# PCB_project.net
KiCad netlist of a schematic drawn in EAGLE
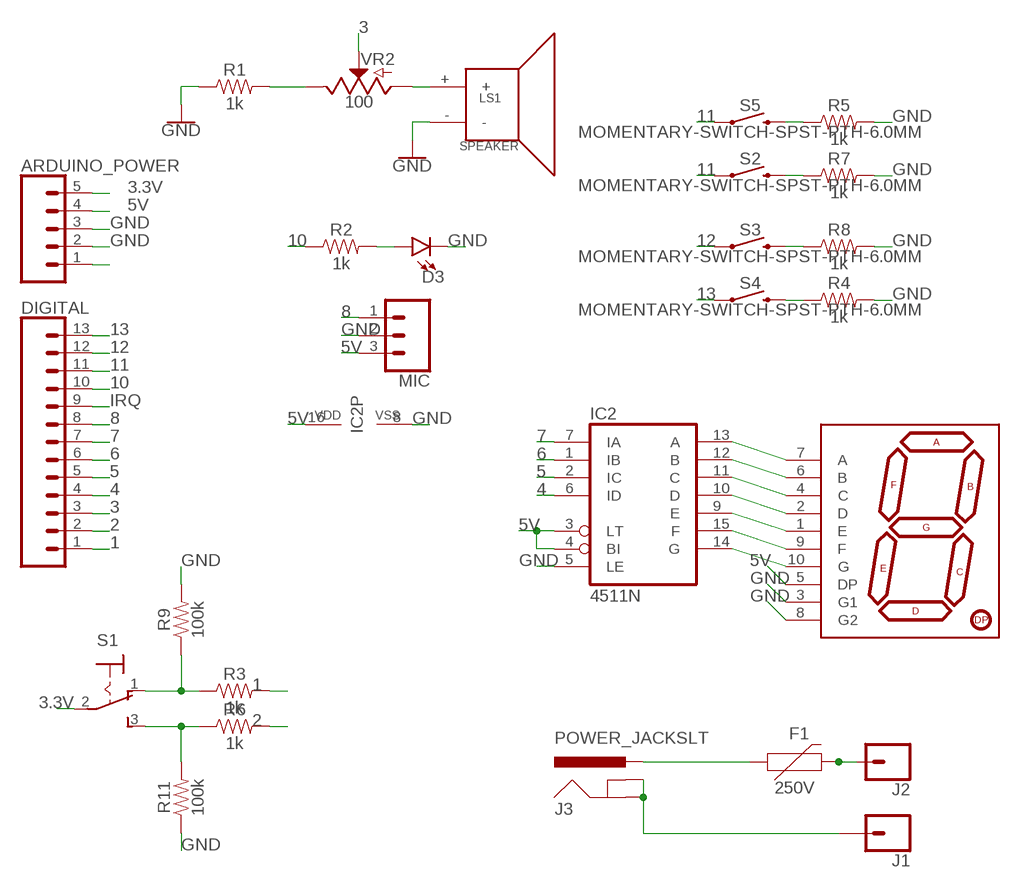
[diagram p0: schematic, sheet 1]

(export (version "E")
  (design (tool "Eeschema 10.0.6"))
  (components
    (comp (ref "ARDUINO_POWER")
      (value "CONN_05")
      (footprint "eagle-import:1X05")
      (libsource (lib "eagle-import") (part "CONN_05"))
    )
    (comp (ref "D3")
      (value "LED-3MM-NO_SILK")
      (footprint "eagle-import:LED_3MM-NS")
      (libsource (lib "eagle-import") (part "LED-3MM-NO_SILK"))
    )
    (comp (ref "DIGITAL")
      (value "CONN_13")
      (footprint "eagle-import:1X13")
      (libsource (lib "eagle-import") (part "CONN_13"))
    )
    (comp (ref "F1")
      (value "250V")
      (footprint "eagle-import:1206")
      (libsource (lib "eagle-import") (part "PPTC_HALF-AMP"))
    )
    (comp (ref "IC2")
      (value "4511N")
      (footprint "eagle-import:DIL16")
      (libsource (lib "eagle-import") (part "4511N"))
    )
    (comp (ref "J1")
      (value "CONN_01")
      (footprint "eagle-import:1X01")
      (libsource (lib "eagle-import") (part "CONN_01"))
    )
    (comp (ref "J2")
      (value "CONN_01")
      (footprint "eagle-import:1X01")
      (libsource (lib "eagle-import") (part "CONN_01"))
    )
    (comp (ref "J3")
      (value "POWER_JACKSLT")
      (footprint "eagle-import:POWER_JACK_SLOT")
      (libsource (lib "eagle-import") (part "POWER_JACKSLT"))
    )
    (comp (ref "LS1")
      (value "SPEAKER")
      (footprint "eagle-import:PCB_MOUNT_SPEAKER")
      (libsource (lib "eagle-import") (part "SPEAKER"))
    )
    (comp (ref "MIC")
      (value "CONN_03")
      (footprint "eagle-import:1X03")
      (libsource (lib "eagle-import") (part "CONN_03"))
    )
    (comp (ref "R1")
      (value "1k")
      (footprint "eagle-import:AXIAL-0.3")
      (libsource (lib "eagle-import") (part "1KOHM-HORIZ-1/4W-1%"))
    )
    (comp (ref "R2")
      (value "1k")
      (footprint "eagle-import:AXIAL-0.3")
      (libsource (lib "eagle-import") (part "1KOHM-HORIZ-1/4W-1%"))
    )
    (comp (ref "R3")
      (value "1k")
      (footprint "eagle-import:AXIAL-0.3")
      (libsource (lib "eagle-import") (part "1KOHM-HORIZ-1/4W-1%"))
    )
    (comp (ref "R4")
      (value "1k")
      (footprint "eagle-import:AXIAL-0.3")
      (libsource (lib "eagle-import") (part "1KOHM-HORIZ-1/4W-1%"))
    )
    (comp (ref "R5")
      (value "1k")
      (footprint "eagle-import:AXIAL-0.3")
      (libsource (lib "eagle-import") (part "1KOHM-HORIZ-1/4W-1%"))
    )
    (comp (ref "R6")
      (value "1k")
      (footprint "eagle-import:AXIAL-0.3")
      (libsource (lib "eagle-import") (part "1KOHM-HORIZ-1/4W-1%"))
    )
    (comp (ref "R7")
      (value "1k")
      (footprint "eagle-import:AXIAL-0.3")
      (libsource (lib "eagle-import") (part "1KOHM-HORIZ-1/4W-1%"))
    )
    (comp (ref "R8")
      (value "1k")
      (footprint "eagle-import:AXIAL-0.3")
      (libsource (lib "eagle-import") (part "1KOHM-HORIZ-1/4W-1%"))
    )
    (comp (ref "R9")
      (value "100k")
      (footprint "eagle-import:AXIAL-0.3")
      (libsource (lib "eagle-import") (part "100KOHM-HORIZ-1/4W-1%"))
    )
    (comp (ref "R11")
      (value "100k")
      (footprint "eagle-import:AXIAL-0.3")
      (libsource (lib "eagle-import") (part "100KOHM-HORIZ-1/4W-1%"))
    )
    (comp (ref "S1")
      (value "320-916")
      (footprint "eagle-import:320-916")
      (libsource (lib "eagle-import") (part "320-916"))
    )
    (comp (ref "S2")
      (value "MOMENTARY-SWITCH-SPST-PTH-6.0MM")
      (footprint "eagle-import:TACTILE_SWITCH_PTH_6.0MM")
      (libsource (lib "eagle-import") (part "MOMENTARY-SWITCH-SPST-PTH-6.0MM"))
    )
    (comp (ref "S3")
      (value "MOMENTARY-SWITCH-SPST-PTH-6.0MM")
      (footprint "eagle-import:TACTILE_SWITCH_PTH_6.0MM")
      (libsource (lib "eagle-import") (part "MOMENTARY-SWITCH-SPST-PTH-6.0MM"))
    )
    (comp (ref "S4")
      (value "MOMENTARY-SWITCH-SPST-PTH-6.0MM")
      (footprint "eagle-import:TACTILE_SWITCH_PTH_6.0MM")
      (libsource (lib "eagle-import") (part "MOMENTARY-SWITCH-SPST-PTH-6.0MM"))
    )
    (comp (ref "S5")
      (value "MOMENTARY-SWITCH-SPST-PTH-6.0MM")
      (footprint "eagle-import:TACTILE_SWITCH_PTH_6.0MM")
      (libsource (lib "eagle-import") (part "MOMENTARY-SWITCH-SPST-PTH-6.0MM"))
    )
    (comp (ref "U$1")
      (value "YSD-160AB3C-8")
      (footprint "eagle-import:7-SEGMENT-1_PTH")
      (libsource (lib "eagle-import") (part "7-SEGMENT-1DIGIT-1INCH-BLUE"))
    )
    (comp (ref "VR2")
      (value "100")
      (footprint "eagle-import:POT-PTH-ALPS")
      (libsource (lib "eagle-import") (part "POTENTIOMETER-PTH-9MM-1/20W-20%"))
    )
  )
  (nets
    (net (code "1") (name "/1") (class "Default")
      (node (ref "DIGITAL") (pin "1") (pinfunction "1_1") (pintype "passive"))
      (node (ref "R3") (pin "P$2") (pinfunction "2_P$2") (pintype "passive"))
    )
    (net (code "2") (name "/2") (class "Default")
      (node (ref "DIGITAL") (pin "2") (pinfunction "2_2") (pintype "passive"))
      (node (ref "R6") (pin "P$2") (pinfunction "2_P$2") (pintype "passive"))
    )
    (net (code "3") (name "/3") (class "Default")
      (node (ref "DIGITAL") (pin "3") (pinfunction "3_3") (pintype "passive"))
      (node (ref "VR2") (pin "P$2") (pinfunction "S_P$2") (pintype "passive"))
    )
    (net (code "4") (name "/3.3V") (class "Default")
      (node (ref "ARDUINO_POWER") (pin "5") (pinfunction "5_5") (pintype "passive"))
      (node (ref "S1") (pin "2") (pinfunction "P_2") (pintype "passive"))
    )
    (net (code "5") (name "/4") (class "Default")
      (node (ref "DIGITAL") (pin "4") (pinfunction "4_4") (pintype "passive"))
      (node (ref "IC2") (pin "6") (pinfunction "ID_6") (pintype "input"))
    )
    (net (code "6") (name "/5") (class "Default")
      (node (ref "DIGITAL") (pin "5") (pinfunction "5_5") (pintype "passive"))
      (node (ref "IC2") (pin "2") (pinfunction "IC_2") (pintype "input"))
    )
    (net (code "7") (name "/5V") (class "Default")
      (node (ref "ARDUINO_POWER") (pin "4") (pinfunction "4_4") (pintype "passive"))
      (node (ref "IC2") (pin "16") (pinfunction "VDD_16") (pintype "power_in"))
      (node (ref "IC2") (pin "3") (pinfunction "LT_3") (pintype "input"))
      (node (ref "IC2") (pin "4") (pinfunction "BI_4") (pintype "input"))
      (node (ref "MIC") (pin "3") (pinfunction "3_3") (pintype "passive"))
      (node (ref "U$1") (pin "5") (pinfunction "DP_5") (pintype "bidirectional"))
    )
    (net (code "8") (name "/6") (class "Default")
      (node (ref "DIGITAL") (pin "6") (pinfunction "6_6") (pintype "passive"))
      (node (ref "IC2") (pin "1") (pinfunction "IB_1") (pintype "input"))
    )
    (net (code "9") (name "/7") (class "Default")
      (node (ref "DIGITAL") (pin "7") (pinfunction "7_7") (pintype "passive"))
      (node (ref "IC2") (pin "7") (pinfunction "IA_7") (pintype "input"))
    )
    (net (code "10") (name "/8") (class "Default")
      (node (ref "DIGITAL") (pin "8") (pinfunction "8_8") (pintype "passive"))
      (node (ref "MIC") (pin "1") (pinfunction "1_1") (pintype "passive"))
    )
    (net (code "11") (name "/10") (class "Default")
      (node (ref "DIGITAL") (pin "10") (pinfunction "10_10") (pintype "passive"))
      (node (ref "R2") (pin "P$1") (pinfunction "1_P$1") (pintype "passive"))
    )
    (net (code "12") (name "/11") (class "Default")
      (node (ref "DIGITAL") (pin "11") (pinfunction "11_11") (pintype "passive"))
      (node (ref "S2") (pin "1") (pinfunction "1_1") (pintype "passive"))
      (node (ref "S5") (pin "1") (pinfunction "1_1") (pintype "passive"))
    )
    (net (code "13") (name "/12") (class "Default")
      (node (ref "DIGITAL") (pin "12") (pinfunction "12_12") (pintype "passive"))
      (node (ref "S3") (pin "1") (pinfunction "1_1") (pintype "passive"))
    )
    (net (code "14") (name "/13") (class "Default")
      (node (ref "DIGITAL") (pin "13") (pinfunction "13_13") (pintype "passive"))
      (node (ref "S4") (pin "1") (pinfunction "1_1") (pintype "passive"))
    )
    (net (code "15") (name "/IRQ") (class "Default")
      (node (ref "DIGITAL") (pin "9") (pinfunction "9_9") (pintype "passive"))
    )
    (net (code "16") (name "GND") (class "Default")
      (node (ref "ARDUINO_POWER") (pin "2") (pinfunction "2_2") (pintype "passive"))
      (node (ref "ARDUINO_POWER") (pin "3") (pinfunction "3_3") (pintype "passive"))
      (node (ref "D3") (pin "K") (pinfunction "C_K") (pintype "passive"))
      (node (ref "IC2") (pin "5") (pinfunction "LE_5") (pintype "input"))
      (node (ref "IC2") (pin "8") (pinfunction "VSS_8") (pintype "power_in"))
      (node (ref "LS1") (pin "-") (pinfunction "-_-") (pintype "bidirectional"))
      (node (ref "MIC") (pin "2") (pinfunction "2_2") (pintype "passive"))
      (node (ref "R1") (pin "P$1") (pinfunction "1_P$1") (pintype "passive"))
      (node (ref "R11") (pin "P$1") (pinfunction "1_P$1") (pintype "passive"))
      (node (ref "R4") (pin "P$2") (pinfunction "2_P$2") (pintype "passive"))
      (node (ref "R5") (pin "P$2") (pinfunction "2_P$2") (pintype "passive"))
      (node (ref "R7") (pin "P$2") (pinfunction "2_P$2") (pintype "passive"))
      (node (ref "R8") (pin "P$2") (pinfunction "2_P$2") (pintype "passive"))
      (node (ref "R9") (pin "P$2") (pinfunction "2_P$2") (pintype "passive"))
      (node (ref "U$1") (pin "3") (pinfunction "G1_3") (pintype "bidirectional"))
      (node (ref "U$1") (pin "8") (pinfunction "G2_8") (pintype "bidirectional"))
    )
    (net (code "17") (name "Net-(F1-Pad1)") (class "Default")
      (node (ref "F1") (pin "1") (pinfunction "1_1") (pintype "bidirectional"))
      (node (ref "J3") (pin "PWR") (pinfunction "PWR_PWR") (pintype "bidirectional"))
    )
    (net (code "18") (name "Net-(F1-Pad2)") (class "Default")
      (node (ref "F1") (pin "2") (pinfunction "2_2") (pintype "bidirectional"))
      (node (ref "J2") (pin "1") (pinfunction "1_1") (pintype "passive"))
    )
    (net (code "19") (name "Net-(IC2A-A)") (class "Default")
      (node (ref "IC2") (pin "13") (pinfunction "A_13") (pintype "output"))
      (node (ref "U$1") (pin "7") (pinfunction "A_7") (pintype "bidirectional"))
    )
    (net (code "20") (name "Net-(IC2A-B)") (class "Default")
      (node (ref "IC2") (pin "12") (pinfunction "B_12") (pintype "output"))
      (node (ref "U$1") (pin "6") (pinfunction "B_6") (pintype "bidirectional"))
    )
    (net (code "21") (name "Net-(IC2A-C)") (class "Default")
      (node (ref "IC2") (pin "11") (pinfunction "C_11") (pintype "output"))
      (node (ref "U$1") (pin "4") (pinfunction "C_4") (pintype "bidirectional"))
    )
    (net (code "22") (name "Net-(IC2A-D)") (class "Default")
      (node (ref "IC2") (pin "10") (pinfunction "D_10") (pintype "output"))
      (node (ref "U$1") (pin "2") (pinfunction "D_2") (pintype "bidirectional"))
    )
    (net (code "23") (name "Net-(IC2A-E)") (class "Default")
      (node (ref "IC2") (pin "9") (pinfunction "E_9") (pintype "output"))
      (node (ref "U$1") (pin "1") (pinfunction "E_1") (pintype "bidirectional"))
    )
    (net (code "24") (name "Net-(IC2A-F)") (class "Default")
      (node (ref "IC2") (pin "15") (pinfunction "F_15") (pintype "output"))
      (node (ref "U$1") (pin "9") (pinfunction "F_9") (pintype "bidirectional"))
    )
    (net (code "25") (name "Net-(IC2A-G)") (class "Default")
      (node (ref "IC2") (pin "14") (pinfunction "G_14") (pintype "output"))
      (node (ref "U$1") (pin "10") (pinfunction "G_10") (pintype "bidirectional"))
    )
    (net (code "26") (name "Net-(J3-GND)") (class "Default")
      (node (ref "J1") (pin "1") (pinfunction "1_1") (pintype "passive"))
      (node (ref "J3") (pin "GND@1") (pinfunction "GNDBREAK_GND@1") (pintype "bidirectional"))
      (node (ref "J3") (pin "GND@2") (pinfunction "GND_GND@2") (pintype "bidirectional"))
    )
    (net (code "27") (name "Net-(R1-2)") (class "Default")
      (node (ref "R1") (pin "P$2") (pinfunction "2_P$2") (pintype "passive"))
      (node (ref "VR2") (pin "P$1") (pinfunction "E_P$1") (pintype "passive"))
    )
    (net (code "28") (name "Net-(R2-2)") (class "Default")
      (node (ref "D3") (pin "A") (pinfunction "A_A") (pintype "passive"))
      (node (ref "R2") (pin "P$2") (pinfunction "2_P$2") (pintype "passive"))
    )
    (net (code "29") (name "Net-(R3-1)") (class "Default")
      (node (ref "R3") (pin "P$1") (pinfunction "1_P$1") (pintype "passive"))
      (node (ref "R9") (pin "P$1") (pinfunction "1_P$1") (pintype "passive"))
      (node (ref "S1") (pin "1") (pinfunction "O_1") (pintype "passive"))
    )
    (net (code "30") (name "Net-(R4-1)") (class "Default")
      (node (ref "R4") (pin "P$1") (pinfunction "1_P$1") (pintype "passive"))
      (node (ref "S4") (pin "3") (pinfunction "2_3") (pintype "passive"))
    )
    (net (code "31") (name "Net-(R5-1)") (class "Default")
      (node (ref "R5") (pin "P$1") (pinfunction "1_P$1") (pintype "passive"))
      (node (ref "S5") (pin "3") (pinfunction "2_3") (pintype "passive"))
    )
    (net (code "32") (name "Net-(R7-1)") (class "Default")
      (node (ref "R7") (pin "P$1") (pinfunction "1_P$1") (pintype "passive"))
      (node (ref "S2") (pin "3") (pinfunction "2_3") (pintype "passive"))
    )
    (net (code "33") (name "Net-(R8-1)") (class "Default")
      (node (ref "R8") (pin "P$1") (pinfunction "1_P$1") (pintype "passive"))
      (node (ref "S3") (pin "3") (pinfunction "2_3") (pintype "passive"))
    )
    (net (code "34") (name "Net-(R11-2)") (class "Default")
      (node (ref "R11") (pin "P$2") (pinfunction "2_P$2") (pintype "passive"))
      (node (ref "R6") (pin "P$1") (pinfunction "1_P$1") (pintype "passive"))
      (node (ref "S1") (pin "3") (pinfunction "S_3") (pintype "passive"))
    )
    (net (code "35") (name "Net-(VR2-A)") (class "Default")
      (node (ref "LS1") (pin "+") (pinfunction "+_+") (pintype "bidirectional"))
      (node (ref "VR2") (pin "P$3") (pinfunction "A_P$3") (pintype "passive"))
    )
    (net (code "36") (name "unconnected-(ARDUINO_POWER-Pad1)") (class "Default")
      (node (ref "ARDUINO_POWER") (pin "1") (pinfunction "1_1") (pintype "passive"))
    )
  )
)
